# 02__RF_Power.net
KiCad netlist of a schematic drawn in Altium Designer
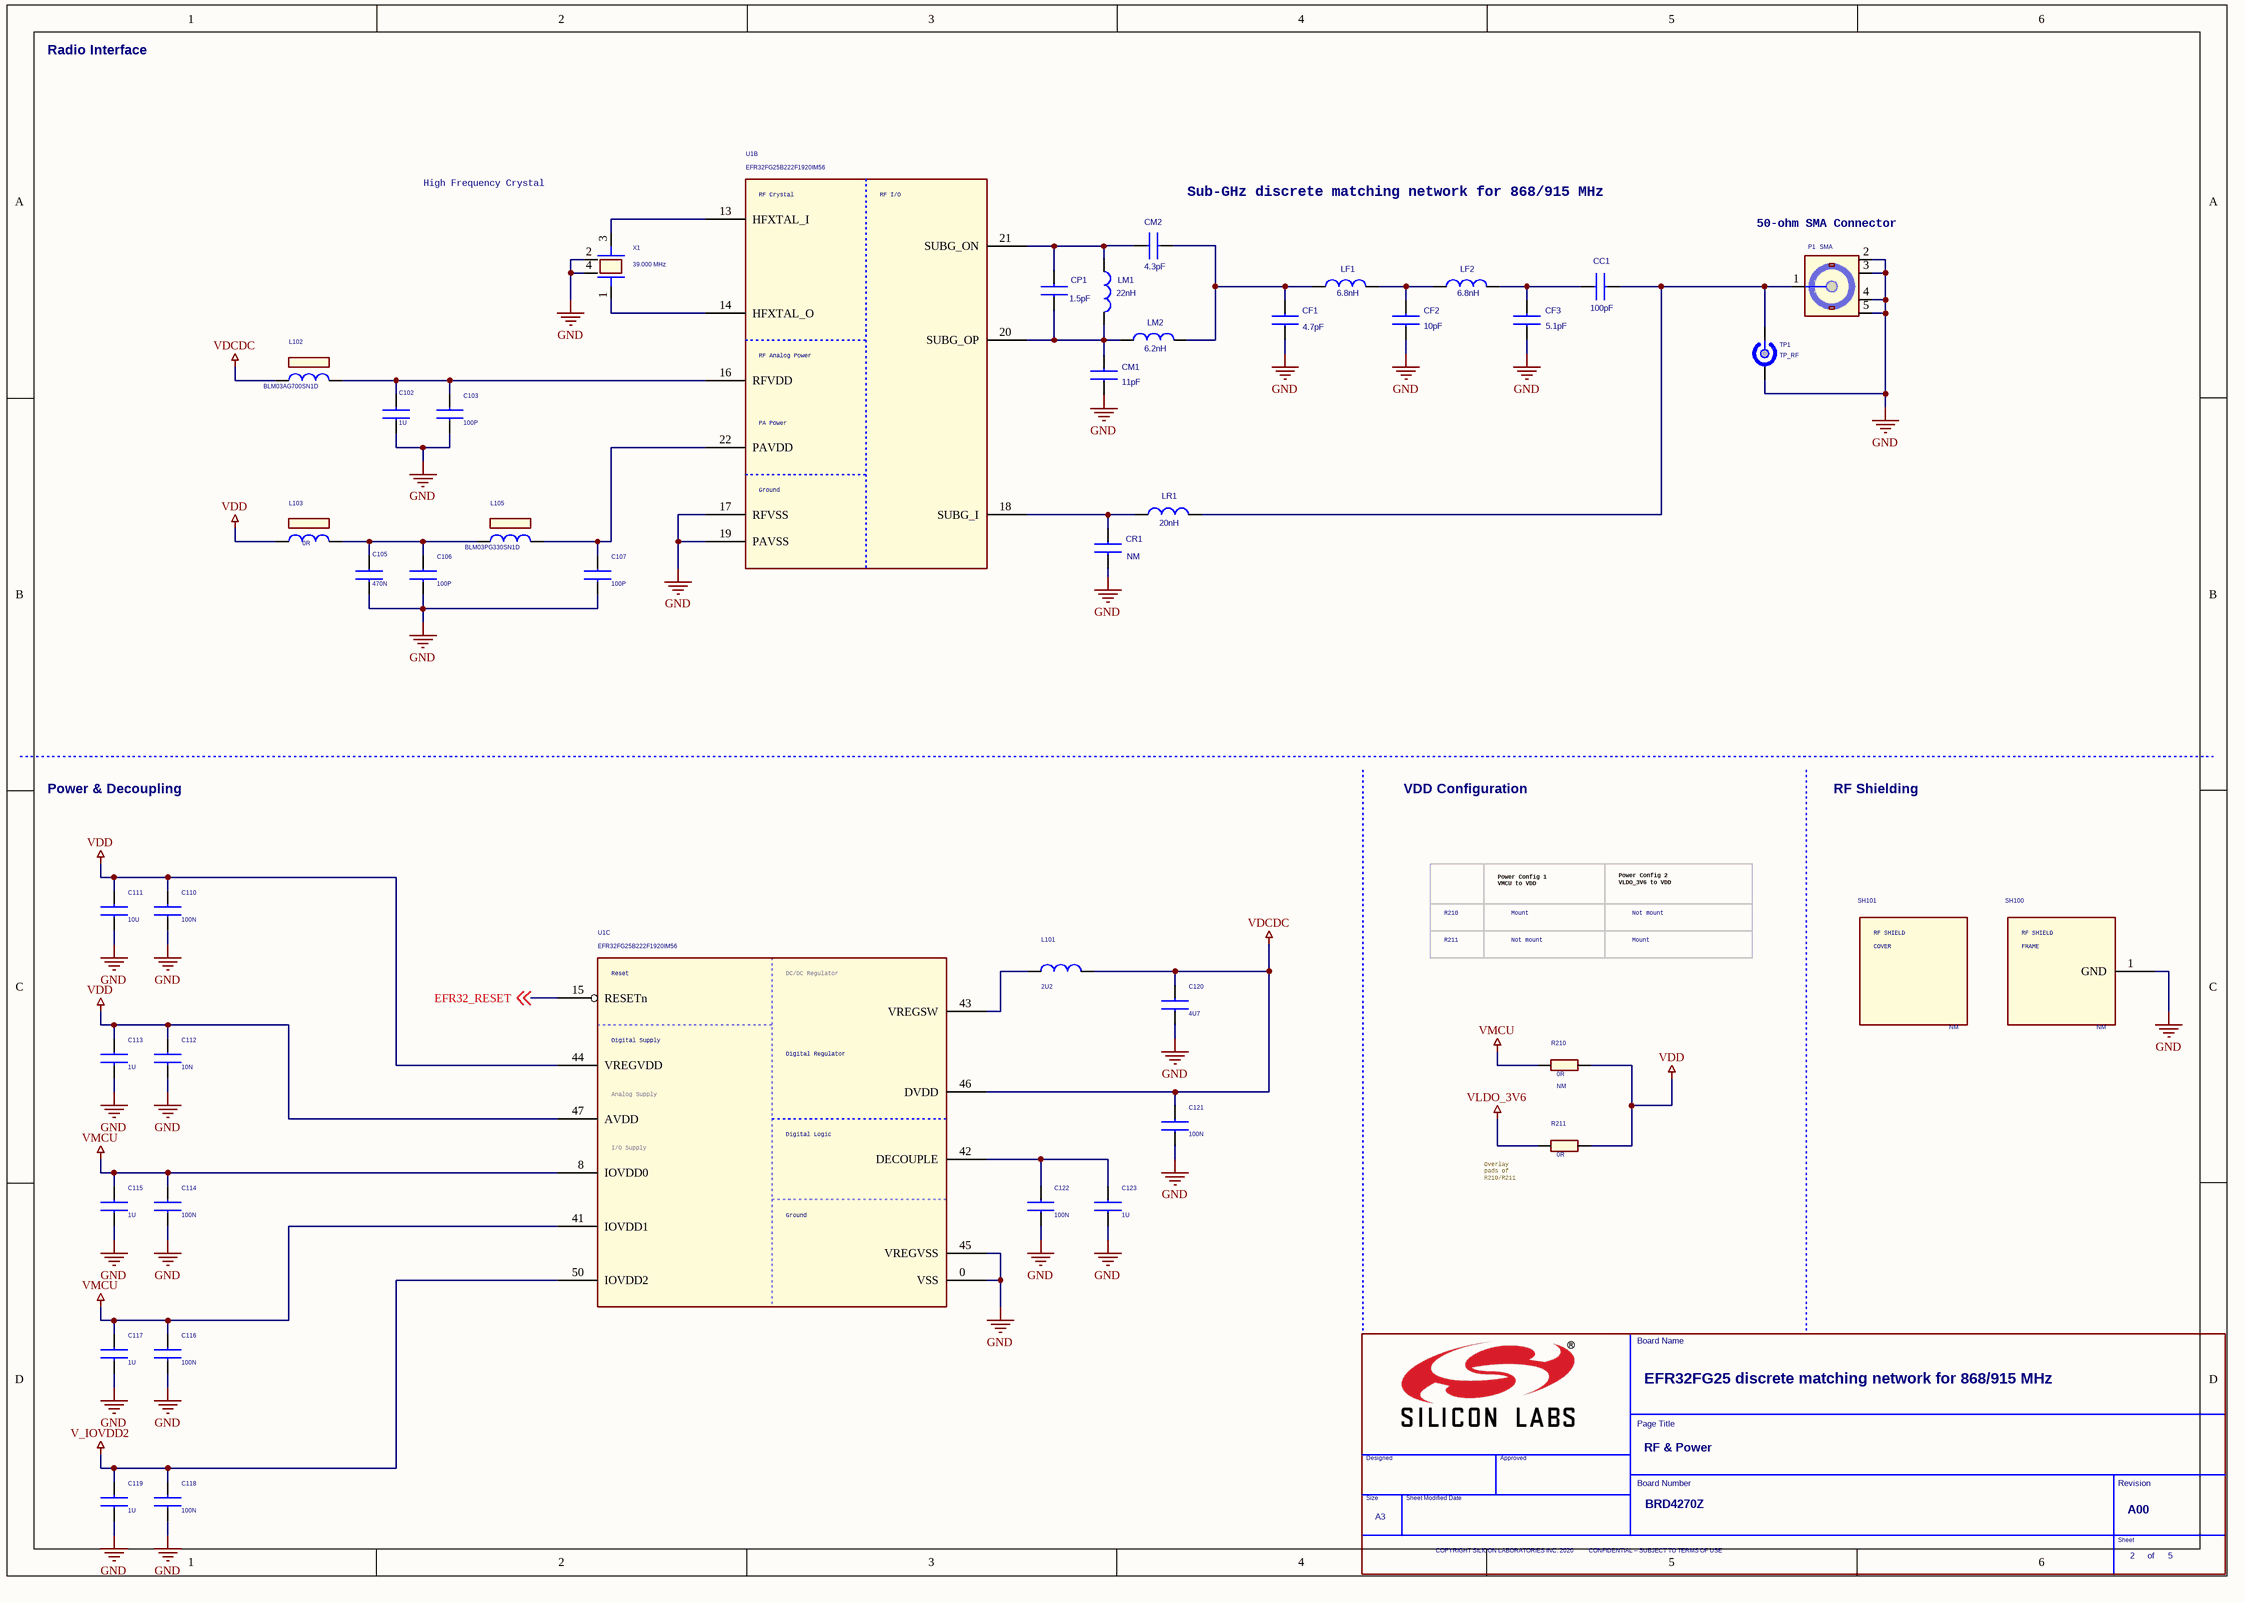
[diagram p0: 02_ RF & Power.SchDoc]

(export (version "E")
  (design (tool "Eeschema 10.0.6"))
  (components
    (comp (ref "C102")
      (value "1U")
      (footprint "C0402_L")
      (fields (field (name "TOLERANCE") "10%"))
      (libsource (lib "*") (part "C0402"))
    )
    (comp (ref "C103")
      (value "100P")
      (footprint "C0201_L")
      (fields (field (name "TOLERANCE") "5%"))
      (libsource (lib "*") (part "C0201"))
    )
    (comp (ref "C105")
      (value "470N")
      (footprint "C0402_L")
      (fields (field (name "TOLERANCE") "10%"))
      (libsource (lib "*") (part "C0402"))
    )
    (comp (ref "C106")
      (value "100P")
      (footprint "C0201_L")
      (fields (field (name "TOLERANCE") "5%"))
      (libsource (lib "*") (part "C0201"))
    )
    (comp (ref "C107")
      (value "100P")
      (footprint "C0201_L")
      (fields (field (name "TOLERANCE") "5%"))
      (libsource (lib "*") (part "C0201"))
    )
    (comp (ref "C110")
      (value "100N")
      (footprint "C0201_L")
      (fields (field (name "TOLERANCE") "20%"))
      (libsource (lib "*") (part "C0201"))
    )
    (comp (ref "C111")
      (value "10U")
      (footprint "C0603_L")
      (fields (field (name "TOLERANCE") "20%"))
      (libsource (lib "*") (part "C0603"))
    )
    (comp (ref "C112")
      (value "10N")
      (footprint "C0201_L")
      (fields (field (name "TOLERANCE") "10%"))
      (libsource (lib "*") (part "C0201"))
    )
    (comp (ref "C113")
      (value "1U")
      (footprint "C0402_L")
      (fields (field (name "TOLERANCE") "10%"))
      (libsource (lib "*") (part "C0402"))
    )
    (comp (ref "C114")
      (value "100N")
      (footprint "C0201_L")
      (fields (field (name "TOLERANCE") "20%"))
      (libsource (lib "*") (part "C0201"))
    )
    (comp (ref "C115")
      (value "1U")
      (footprint "C0402_L")
      (fields (field (name "TOLERANCE") "10%"))
      (libsource (lib "*") (part "C0402"))
    )
    (comp (ref "C116")
      (value "100N")
      (footprint "C0201_L")
      (fields (field (name "TOLERANCE") "20%"))
      (libsource (lib "*") (part "C0201"))
    )
    (comp (ref "C117")
      (value "1U")
      (footprint "C0402_L")
      (fields (field (name "TOLERANCE") "10%"))
      (libsource (lib "*") (part "C0402"))
    )
    (comp (ref "C118")
      (value "100N")
      (footprint "C0201_L")
      (fields (field (name "TOLERANCE") "20%"))
      (libsource (lib "*") (part "C0201"))
    )
    (comp (ref "C119")
      (value "1U")
      (footprint "C0402_L")
      (fields (field (name "TOLERANCE") "10%"))
      (libsource (lib "*") (part "C0402"))
    )
    (comp (ref "C120")
      (value "4U7")
      (footprint "C0603_L")
      (fields (field (name "TOLERANCE") "10%"))
      (libsource (lib "*") (part "C0603"))
    )
    (comp (ref "C121")
      (value "100N")
      (footprint "C0201_L")
      (fields (field (name "TOLERANCE") "20%"))
      (libsource (lib "*") (part "C0201"))
    )
    (comp (ref "C122")
      (value "100N")
      (footprint "C0201_L")
      (fields (field (name "TOLERANCE") "20%"))
      (libsource (lib "*") (part "C0201"))
    )
    (comp (ref "C123")
      (value "1U")
      (footprint "C0402_L")
      (fields (field (name "TOLERANCE") "10%"))
      (libsource (lib "*") (part "C0402"))
    )
    (comp (ref "CC1")
      (value "100pF")
      (footprint "C0201_L")
      (fields (field (name "TOLERANCE") "±0.05P") (field (name "MFG") "Murata"))
      (libsource (lib "*") (part "C0201"))
    )
    (comp (ref "CF1")
      (value "4.7pF")
      (footprint "C0201_L")
      (fields (field (name "TOLERANCE") "±0.1P") (field (name "MFG") "Murata"))
      (libsource (lib "*") (part "C0201"))
    )
    (comp (ref "CF2")
      (value "10pF")
      (footprint "C0201_L")
      (fields (field (name "TOLERANCE") "±0.1P") (field (name "MFG") "Murata"))
      (libsource (lib "*") (part "C0201"))
    )
    (comp (ref "CF3")
      (value "5.1pF")
      (footprint "C0201_L")
      (fields (field (name "TOLERANCE") "±0.05P") (field (name "MFG") "Murata"))
      (libsource (lib "*") (part "C0201"))
    )
    (comp (ref "CM1")
      (value "11pF")
      (footprint "C0201_L")
      (fields (field (name "TOLERANCE") "±0.1P") (field (name "MFG") "Murata"))
      (libsource (lib "*") (part "C0201"))
    )
    (comp (ref "CM2")
      (value "4.3pF")
      (footprint "C0201_L")
      (fields (field (name "TOLERANCE") "±0.05P") (field (name "MFG") "Murata"))
      (libsource (lib "*") (part "C0201"))
    )
    (comp (ref "CP1")
      (value "1.5pF")
      (footprint "C0201_L")
      (fields (field (name "TOLERANCE") "±0.1P") (field (name "MFG") "Murata"))
      (libsource (lib "*") (part "C0201"))
    )
    (comp (ref "CR1")
      (value "Unused")
      (footprint "C0201_L")
      (fields
        (field (name "TOLERANCE") "±0.05P")
        (field (name "NOT MOUNTED") "NM")
        (field (name "MFG") "Murata")
      )
      (libsource (lib "*") (part "C0201"))
    )
    (comp (ref "L101")
      (value "2U2")
      (footprint "COIL_1008_L")
      (fields (field (name "MFG") "Murata") (field (name "TOLERANCE") "+/-20%"))
      (libsource (lib "*") (part "L1008"))
    )
    (comp (ref "L102")
      (value "BLM03AG700SN1D")
      (footprint "COIL_MUR_BLM03_0201")
      (fields (field (name "MFG") "Murata"))
      (libsource (lib "*") (part "BLM03AX"))
    )
    (comp (ref "L103") (value "0R") (footprint "COIL_MUR_BLM03_0201") (libsource (lib "*") (part "BLM03AX")))
    (comp (ref "L105")
      (value "BLM03PG330SN1D")
      (footprint "COIL_MUR_BLM03_0201")
      (fields (field (name "MFG") "Murata"))
      (libsource (lib "*") (part "BLM03AX"))
    )
    (comp (ref "LF1")
      (value "6.8nH")
      (footprint "COIL_0201_L")
      (fields (field (name "TOLERANCE") "±3%") (field (name "MFG") "Murata"))
      (libsource (lib "*") (part "L0201"))
    )
    (comp (ref "LF2")
      (value "6.8nH")
      (footprint "COIL_0201_L")
      (fields (field (name "TOLERANCE") "±3%") (field (name "MFG") "Murata"))
      (libsource (lib "*") (part "L0201"))
    )
    (comp (ref "LM1")
      (value "22nH")
      (footprint "COIL_0201_L")
      (fields (field (name "TOLERANCE") "±0.1N") (field (name "MFG") "Murata"))
      (libsource (lib "*") (part "L0201"))
    )
    (comp (ref "LM2") (value "6.2nH") (footprint "COIL_0201_L") (libsource (lib "*") (part "L0201")))
    (comp (ref "LR1")
      (value "20nH")
      (footprint "COIL_0201_L")
      (fields (field (name "TOLERANCE") "±3%") (field (name "MFG") "Murata"))
      (libsource (lib "*") (part "L0201"))
    )
    (comp (ref "P1")
      (value "SMA")
      (footprint "TE_SMA_1814832_TH_VER")
      (fields (field (name "MFG") "Wellshow"))
      (libsource (lib "*") (part "SMA_TH_WELLSHOW"))
    )
    (comp (ref "R210")
      (value "0R")
      (footprint "R0402_L")
      (fields (field (name "NOT MOUNTED") "NM"))
      (libsource (lib "*") (part "R0402"))
    )
    (comp (ref "R211") (value "0R") (footprint "R0402_L") (libsource (lib "*") (part "R0402")))
    (comp (ref "SH100")
      (value "RF_SHIELD_FRAME_BMI-S-203-F")
      (footprint "LAIRD_BMI-S-203-F")
      (fields (field (name "NOT MOUNTED") "NM") (field (name "MFG") "Laird Technologies"))
      (libsource (lib "*") (part "RF_SHIELD_FRAME_BMI-S-203-F"))
    )
    (comp (ref "SH101")
      (value "RF_SHIELD_COVER_BMI-S-203-C")
      (fields (field (name "MFG") "Laird Technologies") (field (name "NOT MOUNTED") "NM"))
      (libsource (lib "*") (part "RF_SHIELD_COVER_BMI-S-203-C"))
    )
    (comp (ref "TP1")
      (value "TP_RF")
      (footprint "TP_INGUN_50OHM_PARTIAL")
      (libsource (lib "*") (part "TP_RF"))
    )
    (comp (ref "U1")
      (value "EFR32FG25B222F1920IM56")
      (footprint "QFN56_M040_7.0X7.0_EP_SL")
      (fields (field (name "MFG") "Silicon Labs"))
      (libsource (lib "*") (part "EFR32xG25_QFN56_HFCLKOUT"))
    )
    (comp (ref "X1")
      (value "39.000 MHz")
      (footprint "X_SSS_DSX211SH_2.05X1.65-4")
      (fields (field (name "MFG") "Tai-Saw"))
      (libsource (lib "*") (part "DSX211SH"))
    )
  )
  (nets
    (net (code "1") (name "EFR32_RESET") (class "Default")
      (node (ref "U1") (pin "15") (pinfunction "RESETn_15") (pintype "passive"))
    )
    (net (code "2") (name "GND") (class "Default")
      (node (ref "C102") (pin "2") (pinfunction "2_2") (pintype "passive"))
      (node (ref "C103") (pin "2") (pinfunction "2_2") (pintype "passive"))
      (node (ref "C105") (pin "2") (pinfunction "2_2") (pintype "passive"))
      (node (ref "C106") (pin "2") (pinfunction "2_2") (pintype "passive"))
      (node (ref "C107") (pin "2") (pinfunction "2_2") (pintype "passive"))
      (node (ref "C110") (pin "2") (pinfunction "2_2") (pintype "passive"))
      (node (ref "C111") (pin "2") (pinfunction "2_2") (pintype "passive"))
      (node (ref "C112") (pin "2") (pinfunction "2_2") (pintype "passive"))
      (node (ref "C113") (pin "2") (pinfunction "2_2") (pintype "passive"))
      (node (ref "C114") (pin "2") (pinfunction "2_2") (pintype "passive"))
      (node (ref "C115") (pin "2") (pinfunction "2_2") (pintype "passive"))
      (node (ref "C116") (pin "2") (pinfunction "2_2") (pintype "passive"))
      (node (ref "C117") (pin "2") (pinfunction "2_2") (pintype "passive"))
      (node (ref "C118") (pin "2") (pinfunction "2_2") (pintype "passive"))
      (node (ref "C119") (pin "2") (pinfunction "2_2") (pintype "passive"))
      (node (ref "C120") (pin "2") (pinfunction "2_2") (pintype "passive"))
      (node (ref "C121") (pin "2") (pinfunction "2_2") (pintype "passive"))
      (node (ref "C122") (pin "2") (pinfunction "2_2") (pintype "passive"))
      (node (ref "C123") (pin "2") (pinfunction "2_2") (pintype "passive"))
      (node (ref "CF1") (pin "2") (pinfunction "2_2") (pintype "passive"))
      (node (ref "CF2") (pin "2") (pinfunction "2_2") (pintype "passive"))
      (node (ref "CF3") (pin "2") (pinfunction "2_2") (pintype "passive"))
      (node (ref "CM1") (pin "2") (pinfunction "2_2") (pintype "passive"))
      (node (ref "CR1") (pin "2") (pinfunction "2_2") (pintype "passive"))
      (node (ref "P1") (pin "2") (pinfunction "GND1_2") (pintype "passive"))
      (node (ref "P1") (pin "3") (pinfunction "GND2_3") (pintype "passive"))
      (node (ref "P1") (pin "4") (pinfunction "GND3_4") (pintype "passive"))
      (node (ref "P1") (pin "5") (pinfunction "GND4_5") (pintype "passive"))
      (node (ref "SH100") (pin "1") (pinfunction "GND_1") (pintype "passive"))
      (node (ref "TP1") (pin "2") (pinfunction "GND_2") (pintype "power_in"))
      (node (ref "U1") (pin "0") (pinfunction "VSS_0") (pintype "power_in"))
      (node (ref "U1") (pin "17") (pinfunction "RFVSS_17") (pintype "passive"))
      (node (ref "U1") (pin "19") (pinfunction "PAVSS_19") (pintype "passive"))
      (node (ref "U1") (pin "45") (pinfunction "VREGVSS_45") (pintype "passive"))
      (node (ref "X1") (pin "2") (pinfunction "2_2") (pintype "passive"))
      (node (ref "X1") (pin "4") (pinfunction "4_4") (pintype "passive"))
    )
    (net (code "3") (name "Net-(C105-Pad1)") (class "Default")
      (node (ref "C105") (pin "1") (pinfunction "1_1") (pintype "passive"))
      (node (ref "C106") (pin "1") (pinfunction "1_1") (pintype "passive"))
      (node (ref "L103") (pin "2") (pinfunction "2_2") (pintype "passive"))
      (node (ref "L105") (pin "1") (pinfunction "1_1") (pintype "passive"))
    )
    (net (code "4") (name "Net-(CC1-Pad1)") (class "Default")
      (node (ref "CC1") (pin "1") (pinfunction "1_1") (pintype "passive"))
      (node (ref "CF3") (pin "1") (pinfunction "1_1") (pintype "passive"))
      (node (ref "LF2") (pin "2") (pinfunction "2_2") (pintype "passive"))
    )
    (net (code "5") (name "Net-(CF1-Pad1)") (class "Default")
      (node (ref "CF1") (pin "1") (pinfunction "1_1") (pintype "passive"))
      (node (ref "CM2") (pin "2") (pinfunction "2_2") (pintype "passive"))
      (node (ref "LF1") (pin "1") (pinfunction "1_1") (pintype "passive"))
      (node (ref "LM2") (pin "2") (pinfunction "2_2") (pintype "passive"))
    )
    (net (code "6") (name "Net-(CF2-Pad1)") (class "Default")
      (node (ref "CF2") (pin "1") (pinfunction "1_1") (pintype "passive"))
      (node (ref "LF1") (pin "2") (pinfunction "2_2") (pintype "passive"))
      (node (ref "LF2") (pin "1") (pinfunction "1_1") (pintype "passive"))
    )
    (net (code "7") (name "Net-(P1-SIGNAL)") (class "Default")
      (node (ref "CC1") (pin "2") (pinfunction "2_2") (pintype "passive"))
      (node (ref "LR1") (pin "2") (pinfunction "2_2") (pintype "passive"))
      (node (ref "P1") (pin "1") (pinfunction "SIGNAL_1") (pintype "passive"))
      (node (ref "TP1") (pin "1") (pinfunction "RF_1") (pintype "passive"))
    )
    (net (code "8") (name "Net-(U1B-HFXTAL_I)") (class "Default")
      (node (ref "U1") (pin "13") (pinfunction "HFXTAL_I_13") (pintype "passive"))
      (node (ref "X1") (pin "3") (pinfunction "3_3") (pintype "passive"))
    )
    (net (code "9") (name "Net-(U1B-HFXTAL_O)") (class "Default")
      (node (ref "U1") (pin "14") (pinfunction "HFXTAL_O_14") (pintype "passive"))
      (node (ref "X1") (pin "1") (pinfunction "1_1") (pintype "passive"))
    )
    (net (code "10") (name "Net-(U1B-PAVDD)") (class "Default")
      (node (ref "C107") (pin "1") (pinfunction "1_1") (pintype "passive"))
      (node (ref "L105") (pin "2") (pinfunction "2_2") (pintype "passive"))
      (node (ref "U1") (pin "22") (pinfunction "PAVDD_22") (pintype "passive"))
    )
    (net (code "11") (name "Net-(U1B-RFVDD)") (class "Default")
      (node (ref "C102") (pin "1") (pinfunction "1_1") (pintype "passive"))
      (node (ref "C103") (pin "1") (pinfunction "1_1") (pintype "passive"))
      (node (ref "L102") (pin "2") (pinfunction "2_2") (pintype "passive"))
      (node (ref "U1") (pin "16") (pinfunction "RFVDD_16") (pintype "power_in"))
    )
    (net (code "12") (name "Net-(U1B-SUBG_I)") (class "Default")
      (node (ref "CR1") (pin "1") (pinfunction "1_1") (pintype "passive"))
      (node (ref "LR1") (pin "1") (pinfunction "1_1") (pintype "passive"))
      (node (ref "U1") (pin "18") (pinfunction "SUBG_I_18") (pintype "passive"))
    )
    (net (code "13") (name "Net-(U1B-SUBG_ON)") (class "Default")
      (node (ref "CM2") (pin "1") (pinfunction "1_1") (pintype "passive"))
      (node (ref "CP1") (pin "1") (pinfunction "1_1") (pintype "passive"))
      (node (ref "LM1") (pin "1") (pinfunction "1_1") (pintype "passive"))
      (node (ref "U1") (pin "21") (pinfunction "SUBG_ON_21") (pintype "passive"))
    )
    (net (code "14") (name "Net-(U1B-SUBG_OP)") (class "Default")
      (node (ref "CM1") (pin "1") (pinfunction "1_1") (pintype "passive"))
      (node (ref "CP1") (pin "2") (pinfunction "2_2") (pintype "passive"))
      (node (ref "LM1") (pin "2") (pinfunction "2_2") (pintype "passive"))
      (node (ref "LM2") (pin "1") (pinfunction "1_1") (pintype "passive"))
      (node (ref "U1") (pin "20") (pinfunction "SUBG_OP_20") (pintype "passive"))
    )
    (net (code "15") (name "Net-(U1C-DECOUPLE)") (class "Default")
      (node (ref "C122") (pin "1") (pinfunction "1_1") (pintype "passive"))
      (node (ref "C123") (pin "1") (pinfunction "1_1") (pintype "passive"))
      (node (ref "U1") (pin "42") (pinfunction "DECOUPLE_42") (pintype "power_in"))
    )
    (net (code "16") (name "Net-(U1C-VREGSW)") (class "Default")
      (node (ref "L101") (pin "1") (pinfunction "1_1") (pintype "passive"))
      (node (ref "U1") (pin "43") (pinfunction "VREGSW_43") (pintype "passive"))
    )
    (net (code "17") (name "VDCDC") (class "Default")
      (node (ref "C120") (pin "1") (pinfunction "1_1") (pintype "passive"))
      (node (ref "C121") (pin "1") (pinfunction "1_1") (pintype "passive"))
      (node (ref "L101") (pin "2") (pinfunction "2_2") (pintype "passive"))
      (node (ref "L102") (pin "1") (pinfunction "1_1") (pintype "passive"))
      (node (ref "U1") (pin "46") (pinfunction "DVDD_46") (pintype "power_in"))
    )
    (net (code "18") (name "VDD") (class "Default")
      (node (ref "C110") (pin "1") (pinfunction "1_1") (pintype "passive"))
      (node (ref "C111") (pin "1") (pinfunction "1_1") (pintype "passive"))
      (node (ref "C112") (pin "1") (pinfunction "1_1") (pintype "passive"))
      (node (ref "C113") (pin "1") (pinfunction "1_1") (pintype "passive"))
      (node (ref "L103") (pin "1") (pinfunction "1_1") (pintype "passive"))
      (node (ref "R210") (pin "2") (pinfunction "2_2") (pintype "passive"))
      (node (ref "R211") (pin "2") (pinfunction "2_2") (pintype "passive"))
      (node (ref "U1") (pin "44") (pinfunction "VREGVDD_44") (pintype "passive"))
      (node (ref "U1") (pin "47") (pinfunction "AVDD_47") (pintype "power_in"))
    )
    (net (code "19") (name "VLDO_3V6") (class "Default")
      (node (ref "R211") (pin "1") (pinfunction "1_1") (pintype "passive"))
    )
    (net (code "20") (name "VMCU") (class "Default")
      (node (ref "C114") (pin "1") (pinfunction "1_1") (pintype "passive"))
      (node (ref "C115") (pin "1") (pinfunction "1_1") (pintype "passive"))
      (node (ref "C116") (pin "1") (pinfunction "1_1") (pintype "passive"))
      (node (ref "C117") (pin "1") (pinfunction "1_1") (pintype "passive"))
      (node (ref "R210") (pin "1") (pinfunction "1_1") (pintype "passive"))
      (node (ref "U1") (pin "41") (pinfunction "IOVDD1_41") (pintype "power_in"))
      (node (ref "U1") (pin "8") (pinfunction "IOVDD0_8") (pintype "power_in"))
    )
    (net (code "21") (name "V_IOVDD2") (class "Default")
      (node (ref "C118") (pin "1") (pinfunction "1_1") (pintype "passive"))
      (node (ref "C119") (pin "1") (pinfunction "1_1") (pintype "passive"))
      (node (ref "U1") (pin "50") (pinfunction "IOVDD2_50") (pintype "power_in"))
    )
  )
)
